# IrrigationManager.net
KiCad netlist of a schematic drawn in EAGLE
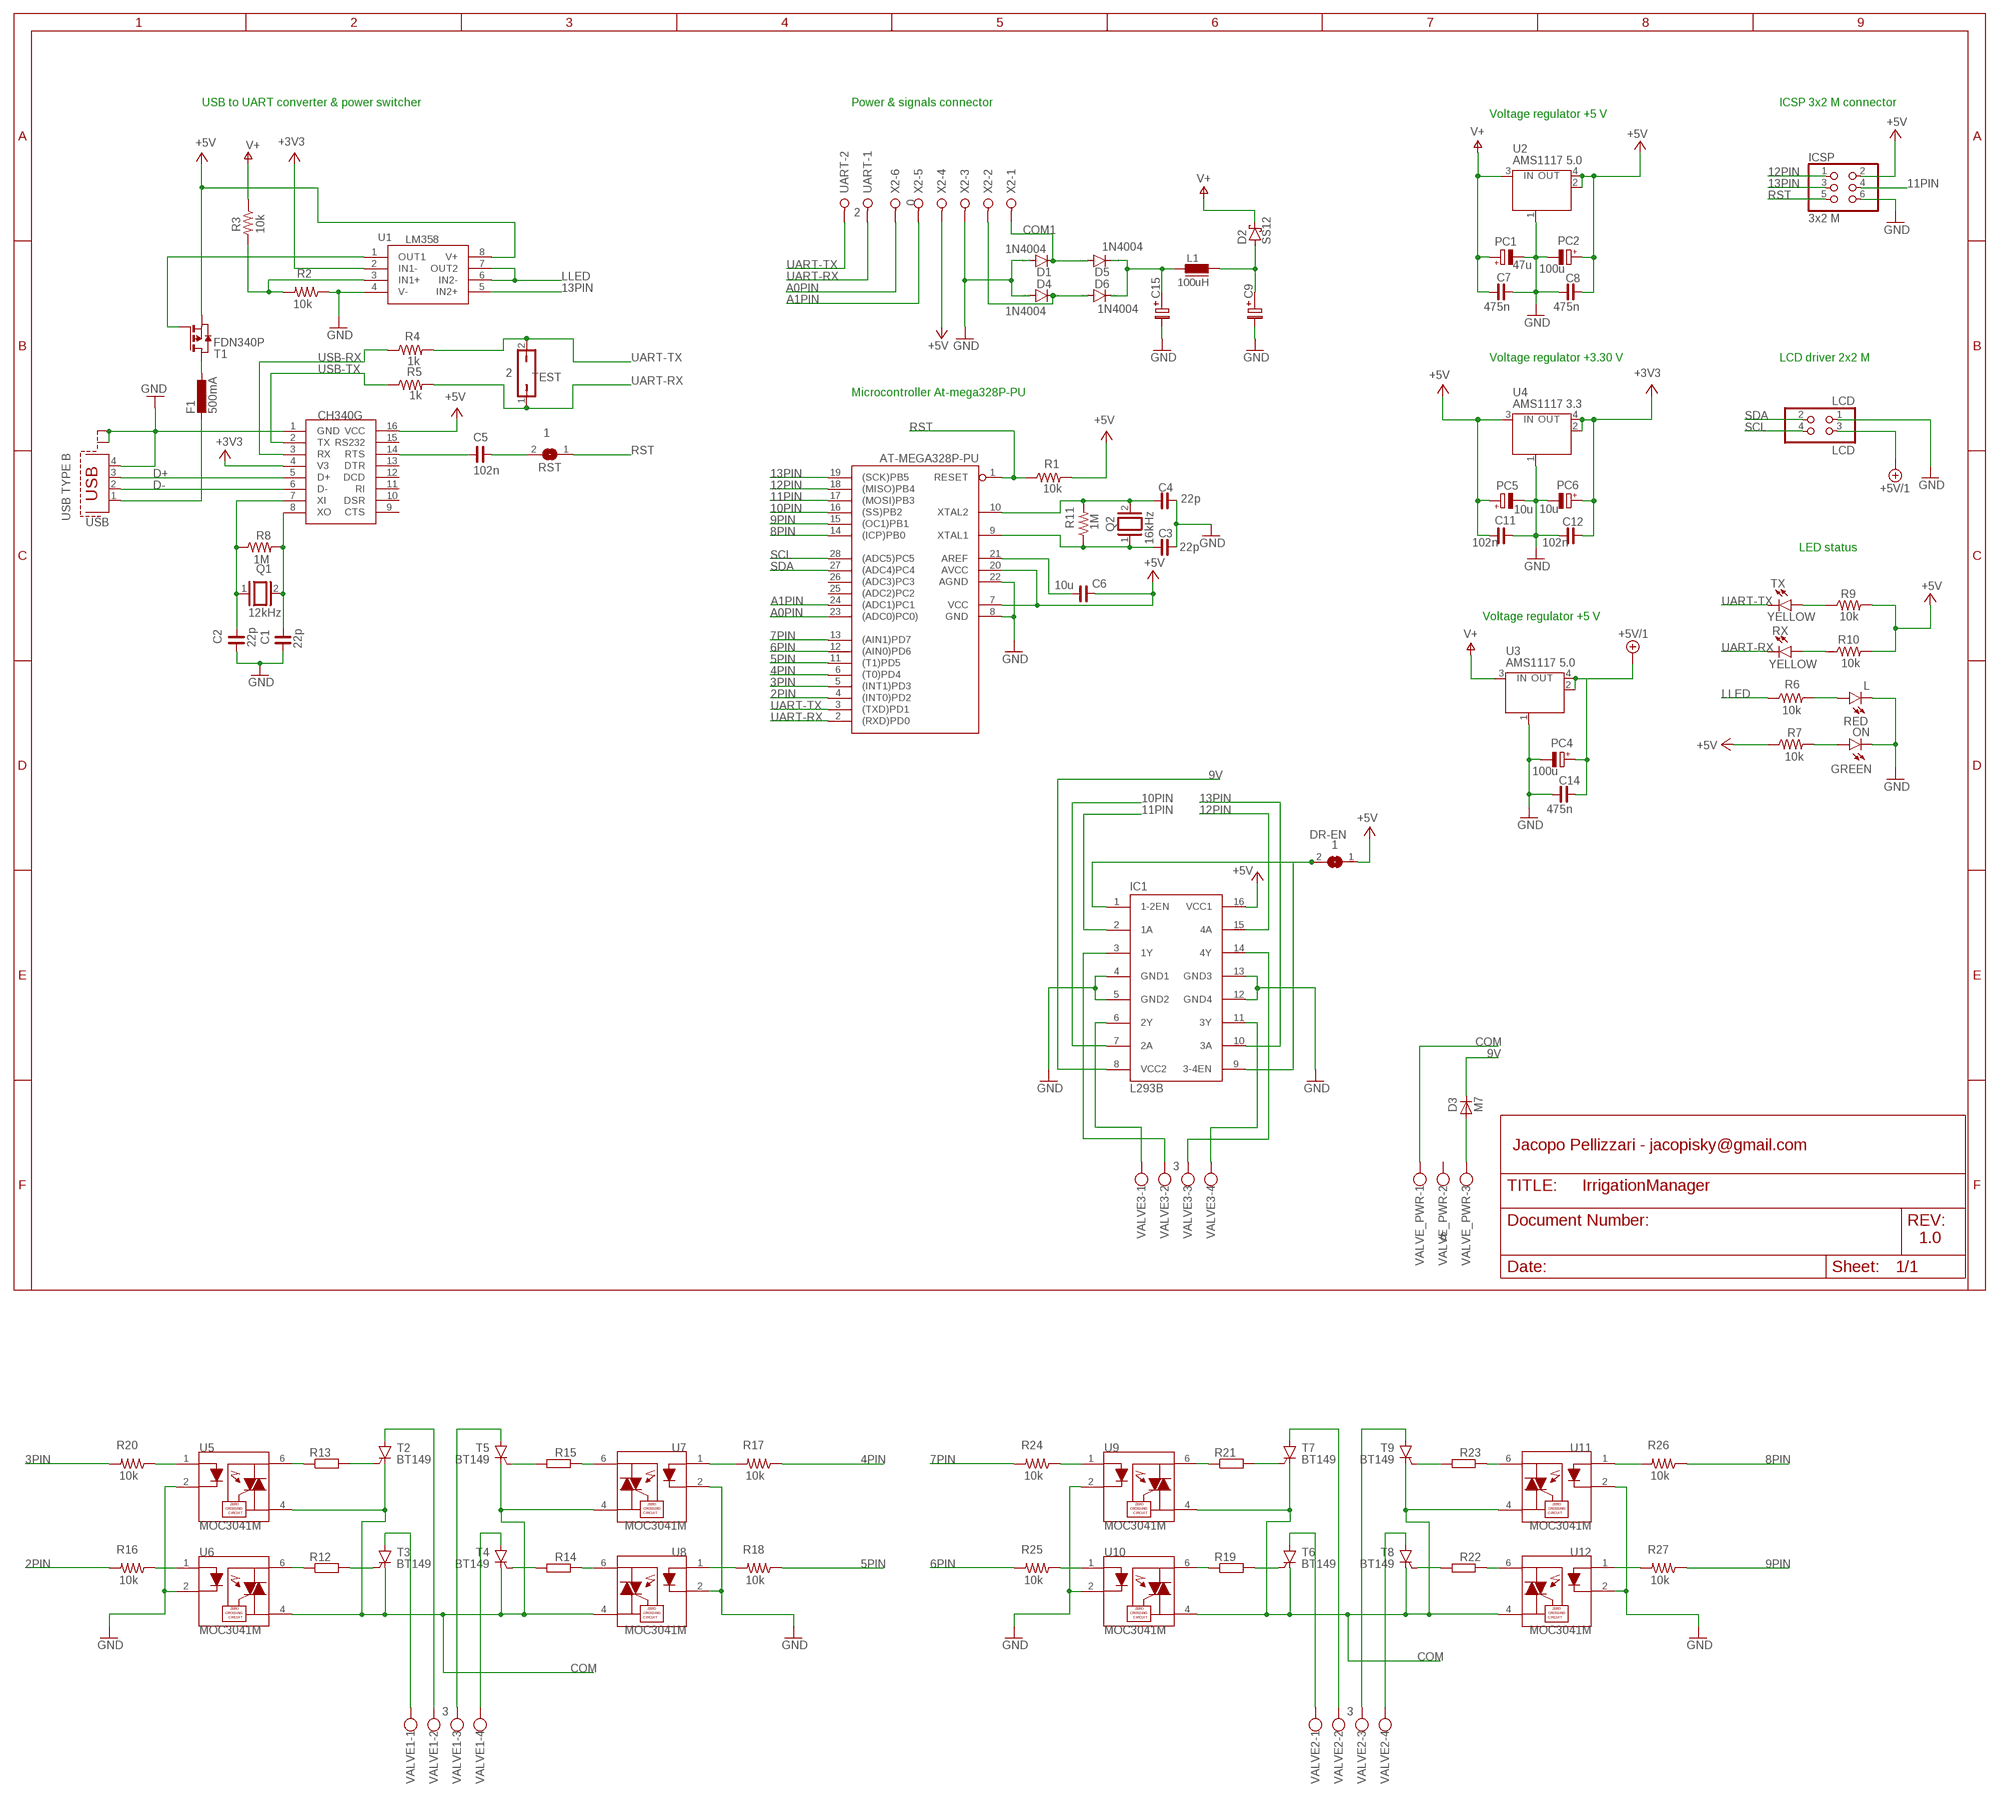
[diagram p0: schematic, sheet 1]

(export (version "E")
  (design (tool "Eeschema 10.0.6"))
  (components
    (comp (ref "AT-MEGA328P-PU")
      (value "ATMEGA328P-PU")
      (footprint "eagle-import:DIL28-3")
      (libsource (lib "eagle-import") (part "ATMEGA328P-PU"))
    )
    (comp (ref "C1")
      (value "22p")
      (footprint "eagle-import:C1206")
      (libsource (lib "eagle-import") (part "C_1206"))
    )
    (comp (ref "C2")
      (value "22p")
      (footprint "eagle-import:C1206")
      (libsource (lib "eagle-import") (part "C_1206"))
    )
    (comp (ref "C3")
      (value "22p")
      (footprint "eagle-import:C1206")
      (libsource (lib "eagle-import") (part "C_1206"))
    )
    (comp (ref "C4")
      (value "22p")
      (footprint "eagle-import:C1206")
      (libsource (lib "eagle-import") (part "C_1206"))
    )
    (comp (ref "C5")
      (value "102n")
      (footprint "eagle-import:C1206")
      (libsource (lib "eagle-import") (part "C_1206"))
    )
    (comp (ref "C6")
      (value "10u")
      (footprint "eagle-import:C1206")
      (libsource (lib "eagle-import") (part "C_1206"))
    )
    (comp (ref "C7")
      (value "475n")
      (footprint "eagle-import:C1206")
      (libsource (lib "eagle-import") (part "C_1206"))
    )
    (comp (ref "C8")
      (value "475n")
      (footprint "eagle-import:C1206")
      (libsource (lib "eagle-import") (part "C_1206"))
    )
    (comp (ref "C9")
      (value "C-PR-5,0X10")
      (footprint "eagle-import:E5,0-10")
      (libsource (lib "eagle-import") (part "C-PR-5,0X10"))
    )
    (comp (ref "C11")
      (value "102n")
      (footprint "eagle-import:C1206")
      (libsource (lib "eagle-import") (part "C_1206"))
    )
    (comp (ref "C12")
      (value "102n")
      (footprint "eagle-import:C1206")
      (libsource (lib "eagle-import") (part "C_1206"))
    )
    (comp (ref "C14")
      (value "475n")
      (footprint "eagle-import:C1206")
      (libsource (lib "eagle-import") (part "C_1206"))
    )
    (comp (ref "C15")
      (value "C-PR-5,0X10")
      (footprint "eagle-import:E5,0-10")
      (libsource (lib "eagle-import") (part "C-PR-5,0X10"))
    )
    (comp (ref "D1")
      (value "1N4004")
      (footprint "eagle-import:DO41-10")
      (libsource (lib "eagle-import") (part "1N4004"))
    )
    (comp (ref "D2")
      (value "SS12")
      (footprint "eagle-import:SMA")
      (fields
        (field (name "DIGIKEY_PART_NUMBER") "SS12FSCT-ND")
        (field (name "MANUFACTURER") "ON Semiconductor")
        (field (name "CREATED_BY") "PCBLayout.com")
      )
      (libsource (lib "eagle-import") (part "SS12"))
    )
    (comp (ref "D3")
      (value "M7")
      (footprint "eagle-import:SMB")
      (libsource (lib "eagle-import") (part "DIODE-SMB"))
    )
    (comp (ref "D4")
      (value "1N4004")
      (footprint "eagle-import:DO41-10")
      (libsource (lib "eagle-import") (part "1N4004"))
    )
    (comp (ref "D5")
      (value "1N4004")
      (footprint "eagle-import:DO41-10")
      (libsource (lib "eagle-import") (part "1N4004"))
    )
    (comp (ref "D6")
      (value "1N4004")
      (footprint "eagle-import:DO41-10")
      (libsource (lib "eagle-import") (part "1N4004"))
    )
    (comp (ref "DR-EN")
      (value "1")
      (footprint "eagle-import:SJ")
      (libsource (lib "eagle-import") (part "SJ"))
    )
    (comp (ref "F1")
      (value "500mA")
      (footprint "eagle-import:L1812")
      (libsource (lib "eagle-import") (part "L-EUL1812"))
    )
    (comp (ref "IC1")
      (value "L293B")
      (footprint "eagle-import:DIL16")
      (fields (field (name "MPN") "L293D"))
      (libsource (lib "eagle-import") (part "L293D"))
    )
    (comp (ref "ICSP")
      (value "3x2 M")
      (footprint "eagle-import:2X03")
      (libsource (lib "eagle-import") (part "PINHD-2X3"))
    )
    (comp (ref "L")
      (value "RED")
      (footprint "eagle-import:CHIPLED_1206")
      (libsource (lib "eagle-import") (part "LEDCHIPLED_1206"))
    )
    (comp (ref "L1")
      (value "100uH")
      (footprint "eagle-import:FASTRON_07HCP_INDUCTOR")
      (libsource (lib "eagle-import") (part "07HCP-4U7"))
    )
    (comp (ref "LCD")
      (value "LCD")
      (footprint "eagle-import:2X02")
      (libsource (lib "eagle-import") (part "PINHD-2X2"))
    )
    (comp (ref "ON")
      (value "GREEN")
      (footprint "eagle-import:CHIPLED_1206")
      (libsource (lib "eagle-import") (part "LEDCHIPLED_1206"))
    )
    (comp (ref "PC1")
      (value "47u")
      (footprint "eagle-import:PANASONIC_D")
      (libsource (lib "eagle-import") (part "CPOL-EUD"))
    )
    (comp (ref "PC2")
      (value "100u")
      (footprint "eagle-import:PANASONIC_D")
      (libsource (lib "eagle-import") (part "CPOL-EUD"))
    )
    (comp (ref "PC4")
      (value "100u")
      (footprint "eagle-import:PANASONIC_D")
      (libsource (lib "eagle-import") (part "CPOL-EUD"))
    )
    (comp (ref "PC5")
      (value "10u")
      (footprint "eagle-import:153CLV-0405")
      (libsource (lib "eagle-import") (part "rcl_334_CPOL-EU153CLV-0405"))
    )
    (comp (ref "PC6")
      (value "10u")
      (footprint "eagle-import:153CLV-0405")
      (libsource (lib "eagle-import") (part "rcl_334_CPOL-EU153CLV-0405"))
    )
    (comp (ref "Q1")
      (value "12kHz")
      (footprint "eagle-import:QS")
      (libsource (lib "eagle-import") (part "XTAL/S"))
    )
    (comp (ref "Q2")
      (value "16kHz")
      (footprint "eagle-import:QS")
      (libsource (lib "eagle-import") (part "XTAL/S"))
    )
    (comp (ref "R1")
      (value "10k")
      (footprint "eagle-import:RES_1206")
      (fields
        (field (name "DIGIKEY_PART_NUMBER") "P0.0ETR-ND")
        (field (name "MANUFACTURER") "Panasonic Electronic Components")
        (field (name "MPN") "ERJ-8GEY0R00V")
        (field (name "CREATED_BY") "PCBLayout.com")
      )
      (libsource (lib "eagle-import") (part "ERJ-8GEY0R00V"))
    )
    (comp (ref "R2")
      (value "10k")
      (footprint "eagle-import:RES_1206")
      (fields
        (field (name "DIGIKEY_PART_NUMBER") "P0.0ETR-ND")
        (field (name "MANUFACTURER") "Panasonic Electronic Components")
        (field (name "MPN") "ERJ-8GEY0R00V")
        (field (name "CREATED_BY") "PCBLayout.com")
      )
      (libsource (lib "eagle-import") (part "ERJ-8GEY0R00V"))
    )
    (comp (ref "R3")
      (value "10k")
      (footprint "eagle-import:RES_1206")
      (fields
        (field (name "DIGIKEY_PART_NUMBER") "P0.0ETR-ND")
        (field (name "MANUFACTURER") "Panasonic Electronic Components")
        (field (name "MPN") "ERJ-8GEY0R00V")
        (field (name "CREATED_BY") "PCBLayout.com")
      )
      (libsource (lib "eagle-import") (part "ERJ-8GEY0R00V"))
    )
    (comp (ref "R4")
      (value "1k")
      (footprint "eagle-import:RES_1206")
      (fields
        (field (name "DIGIKEY_PART_NUMBER") "P0.0ETR-ND")
        (field (name "MANUFACTURER") "Panasonic Electronic Components")
        (field (name "MPN") "ERJ-8GEY0R00V")
        (field (name "CREATED_BY") "PCBLayout.com")
      )
      (libsource (lib "eagle-import") (part "ERJ-8GEY0R00V"))
    )
    (comp (ref "R5")
      (value "1k")
      (footprint "eagle-import:RES_1206")
      (fields
        (field (name "DIGIKEY_PART_NUMBER") "P0.0ETR-ND")
        (field (name "MANUFACTURER") "Panasonic Electronic Components")
        (field (name "MPN") "ERJ-8GEY0R00V")
        (field (name "CREATED_BY") "PCBLayout.com")
      )
      (libsource (lib "eagle-import") (part "ERJ-8GEY0R00V"))
    )
    (comp (ref "R6")
      (value "10k")
      (footprint "eagle-import:RES_1206")
      (fields
        (field (name "DIGIKEY_PART_NUMBER") "P0.0ETR-ND")
        (field (name "MANUFACTURER") "Panasonic Electronic Components")
        (field (name "MPN") "ERJ-8GEY0R00V")
        (field (name "CREATED_BY") "PCBLayout.com")
      )
      (libsource (lib "eagle-import") (part "ERJ-8GEY0R00V"))
    )
    (comp (ref "R7")
      (value "10k")
      (footprint "eagle-import:RES_1206")
      (fields
        (field (name "DIGIKEY_PART_NUMBER") "P0.0ETR-ND")
        (field (name "MANUFACTURER") "Panasonic Electronic Components")
        (field (name "MPN") "ERJ-8GEY0R00V")
        (field (name "CREATED_BY") "PCBLayout.com")
      )
      (libsource (lib "eagle-import") (part "ERJ-8GEY0R00V"))
    )
    (comp (ref "R8")
      (value "1M")
      (footprint "eagle-import:RES_1206")
      (fields
        (field (name "DIGIKEY_PART_NUMBER") "P0.0ETR-ND")
        (field (name "MANUFACTURER") "Panasonic Electronic Components")
        (field (name "MPN") "ERJ-8GEY0R00V")
        (field (name "CREATED_BY") "PCBLayout.com")
      )
      (libsource (lib "eagle-import") (part "ERJ-8GEY0R00V"))
    )
    (comp (ref "R9")
      (value "10k")
      (footprint "eagle-import:RES_1206")
      (fields
        (field (name "DIGIKEY_PART_NUMBER") "P0.0ETR-ND")
        (field (name "MANUFACTURER") "Panasonic Electronic Components")
        (field (name "MPN") "ERJ-8GEY0R00V")
        (field (name "CREATED_BY") "PCBLayout.com")
      )
      (libsource (lib "eagle-import") (part "ERJ-8GEY0R00V"))
    )
    (comp (ref "R10")
      (value "10k")
      (footprint "eagle-import:RES_1206")
      (fields
        (field (name "DIGIKEY_PART_NUMBER") "P0.0ETR-ND")
        (field (name "MANUFACTURER") "Panasonic Electronic Components")
        (field (name "MPN") "ERJ-8GEY0R00V")
        (field (name "CREATED_BY") "PCBLayout.com")
      )
      (libsource (lib "eagle-import") (part "ERJ-8GEY0R00V"))
    )
    (comp (ref "R11")
      (value "1M")
      (footprint "eagle-import:RES_1206")
      (fields
        (field (name "DIGIKEY_PART_NUMBER") "P0.0ETR-ND")
        (field (name "MANUFACTURER") "Panasonic Electronic Components")
        (field (name "MPN") "ERJ-8GEY0R00V")
        (field (name "CREATED_BY") "PCBLayout.com")
      )
      (libsource (lib "eagle-import") (part "ERJ-8GEY0R00V"))
    )
    (comp (ref "R12")
      (value "R-EU_0204/7")
      (footprint "eagle-import:0204_7")
      (libsource (lib "eagle-import") (part "R-EU_0204/7"))
    )
    (comp (ref "R13")
      (value "R-EU_0204/7")
      (footprint "eagle-import:0204_7")
      (libsource (lib "eagle-import") (part "R-EU_0204/7"))
    )
    (comp (ref "R14")
      (value "R-EU_0204/7")
      (footprint "eagle-import:0204_7")
      (libsource (lib "eagle-import") (part "R-EU_0204/7"))
    )
    (comp (ref "R15")
      (value "R-EU_0204/7")
      (footprint "eagle-import:0204_7")
      (libsource (lib "eagle-import") (part "R-EU_0204/7"))
    )
    (comp (ref "R16")
      (value "10k")
      (footprint "eagle-import:RES_1206")
      (fields
        (field (name "DIGIKEY_PART_NUMBER") "P0.0ETR-ND")
        (field (name "MANUFACTURER") "Panasonic Electronic Components")
        (field (name "MPN") "ERJ-8GEY0R00V")
        (field (name "CREATED_BY") "PCBLayout.com")
      )
      (libsource (lib "eagle-import") (part "ERJ-8GEY0R00V"))
    )
    (comp (ref "R17")
      (value "10k")
      (footprint "eagle-import:RES_1206")
      (fields
        (field (name "DIGIKEY_PART_NUMBER") "P0.0ETR-ND")
        (field (name "MANUFACTURER") "Panasonic Electronic Components")
        (field (name "MPN") "ERJ-8GEY0R00V")
        (field (name "CREATED_BY") "PCBLayout.com")
      )
      (libsource (lib "eagle-import") (part "ERJ-8GEY0R00V"))
    )
    (comp (ref "R18")
      (value "10k")
      (footprint "eagle-import:RES_1206")
      (fields
        (field (name "DIGIKEY_PART_NUMBER") "P0.0ETR-ND")
        (field (name "MANUFACTURER") "Panasonic Electronic Components")
        (field (name "MPN") "ERJ-8GEY0R00V")
        (field (name "CREATED_BY") "PCBLayout.com")
      )
      (libsource (lib "eagle-import") (part "ERJ-8GEY0R00V"))
    )
    (comp (ref "R19")
      (value "R-EU_0204/7")
      (footprint "eagle-import:0204_7")
      (libsource (lib "eagle-import") (part "R-EU_0204/7"))
    )
    (comp (ref "R20")
      (value "10k")
      (footprint "eagle-import:RES_1206")
      (fields
        (field (name "DIGIKEY_PART_NUMBER") "P0.0ETR-ND")
        (field (name "MANUFACTURER") "Panasonic Electronic Components")
        (field (name "MPN") "ERJ-8GEY0R00V")
        (field (name "CREATED_BY") "PCBLayout.com")
      )
      (libsource (lib "eagle-import") (part "ERJ-8GEY0R00V"))
    )
    (comp (ref "R21")
      (value "R-EU_0204/7")
      (footprint "eagle-import:0204_7")
      (libsource (lib "eagle-import") (part "R-EU_0204/7"))
    )
    (comp (ref "R22")
      (value "R-EU_0204/7")
      (footprint "eagle-import:0204_7")
      (libsource (lib "eagle-import") (part "R-EU_0204/7"))
    )
    (comp (ref "R23")
      (value "R-EU_0204/7")
      (footprint "eagle-import:0204_7")
      (libsource (lib "eagle-import") (part "R-EU_0204/7"))
    )
    (comp (ref "R24")
      (value "10k")
      (footprint "eagle-import:RES_1206")
      (fields
        (field (name "DIGIKEY_PART_NUMBER") "P0.0ETR-ND")
        (field (name "MANUFACTURER") "Panasonic Electronic Components")
        (field (name "MPN") "ERJ-8GEY0R00V")
        (field (name "CREATED_BY") "PCBLayout.com")
      )
      (libsource (lib "eagle-import") (part "ERJ-8GEY0R00V"))
    )
    (comp (ref "R25")
      (value "10k")
      (footprint "eagle-import:RES_1206")
      (fields
        (field (name "DIGIKEY_PART_NUMBER") "P0.0ETR-ND")
        (field (name "MANUFACTURER") "Panasonic Electronic Components")
        (field (name "MPN") "ERJ-8GEY0R00V")
        (field (name "CREATED_BY") "PCBLayout.com")
      )
      (libsource (lib "eagle-import") (part "ERJ-8GEY0R00V"))
    )
    (comp (ref "R26")
      (value "10k")
      (footprint "eagle-import:RES_1206")
      (fields
        (field (name "DIGIKEY_PART_NUMBER") "P0.0ETR-ND")
        (field (name "MANUFACTURER") "Panasonic Electronic Components")
        (field (name "MPN") "ERJ-8GEY0R00V")
        (field (name "CREATED_BY") "PCBLayout.com")
      )
      (libsource (lib "eagle-import") (part "ERJ-8GEY0R00V"))
    )
    (comp (ref "R27")
      (value "10k")
      (footprint "eagle-import:RES_1206")
      (fields
        (field (name "DIGIKEY_PART_NUMBER") "P0.0ETR-ND")
        (field (name "MANUFACTURER") "Panasonic Electronic Components")
        (field (name "MPN") "ERJ-8GEY0R00V")
        (field (name "CREATED_BY") "PCBLayout.com")
      )
      (libsource (lib "eagle-import") (part "ERJ-8GEY0R00V"))
    )
    (comp (ref "RST") (value "1") (footprint "eagle-import:SJ") (libsource (lib "eagle-import") (part "SJ")))
    (comp (ref "RX")
      (value "YELLOW")
      (footprint "eagle-import:CHIPLED_1206")
      (libsource (lib "eagle-import") (part "LEDCHIPLED_1206"))
    )
    (comp (ref "T1")
      (value "FDN340P")
      (footprint "eagle-import:SOT-23")
      (libsource (lib "eagle-import") (part "PMOSSOT23"))
    )
    (comp (ref "T2")
      (value "BT149")
      (footprint "eagle-import:TO92-4")
      (libsource (lib "eagle-import") (part "BT149"))
    )
    (comp (ref "T3")
      (value "BT149")
      (footprint "eagle-import:TO92-4")
      (libsource (lib "eagle-import") (part "BT149"))
    )
    (comp (ref "T4")
      (value "BT149")
      (footprint "eagle-import:TO92-4")
      (libsource (lib "eagle-import") (part "BT149"))
    )
    (comp (ref "T5")
      (value "BT149")
      (footprint "eagle-import:TO92-4")
      (libsource (lib "eagle-import") (part "BT149"))
    )
    (comp (ref "T6")
      (value "BT149")
      (footprint "eagle-import:TO92-4")
      (libsource (lib "eagle-import") (part "BT149"))
    )
    (comp (ref "T7")
      (value "BT149")
      (footprint "eagle-import:TO92-4")
      (libsource (lib "eagle-import") (part "BT149"))
    )
    (comp (ref "T8")
      (value "BT149")
      (footprint "eagle-import:TO92-4")
      (libsource (lib "eagle-import") (part "BT149"))
    )
    (comp (ref "T9")
      (value "BT149")
      (footprint "eagle-import:TO92-4")
      (libsource (lib "eagle-import") (part "BT149"))
    )
    (comp (ref "TEST")
      (value "2")
      (footprint "eagle-import:JP1")
      (libsource (lib "eagle-import") (part "JP1Q"))
    )
    (comp (ref "TX")
      (value "YELLOW")
      (footprint "eagle-import:CHIPLED_1206")
      (libsource (lib "eagle-import") (part "LEDCHIPLED_1206"))
    )
    (comp (ref "U$1")
      (value "CH340G")
      (footprint "eagle-import:SOIC16")
      (libsource (lib "eagle-import") (part "CH340G"))
    )
    (comp (ref "U1")
      (value "LM358")
      (footprint "eagle-import:LM358DR")
      (fields
        (field (name "DIGIKEY_PART_NUMBER") "296-1014-1-ND")
        (field (name "MANUFACTURER") "Texas Instruments")
        (field (name "MPN") "LM358DR")
        (field (name "CREATED_BY") "PCBLayout.com")
      )
      (libsource (lib "eagle-import") (part "LM358DR"))
    )
    (comp (ref "U2")
      (value "AMS1117 5.0")
      (footprint "eagle-import:SOT223")
      (libsource (lib "eagle-import") (part "MC33269ST-3.3T3"))
    )
    (comp (ref "U3")
      (value "AMS1117 5.0")
      (footprint "eagle-import:SOT223")
      (libsource (lib "eagle-import") (part "MC33269ST-3.3T3"))
    )
    (comp (ref "U4")
      (value "AMS1117 3.3")
      (footprint "eagle-import:SOT223")
      (libsource (lib "eagle-import") (part "MC33269ST-3.3T3"))
    )
    (comp (ref "U5")
      (value "MOC3041M")
      (footprint "eagle-import:DIP762W46P254L889H508Q6")
      (fields (field (name "MF") "ON Semiconductor"))
      (libsource (lib "eagle-import") (part "MOC3041M"))
    )
    (comp (ref "U6")
      (value "MOC3041M")
      (footprint "eagle-import:DIP762W46P254L889H508Q6")
      (fields (field (name "MF") "ON Semiconductor"))
      (libsource (lib "eagle-import") (part "MOC3041M"))
    )
    (comp (ref "U7")
      (value "MOC3041M")
      (footprint "eagle-import:DIP762W46P254L889H508Q6")
      (fields (field (name "MF") "ON Semiconductor"))
      (libsource (lib "eagle-import") (part "MOC3041M"))
    )
    (comp (ref "U8")
      (value "MOC3041M")
      (footprint "eagle-import:DIP762W46P254L889H508Q6")
      (fields (field (name "MF") "ON Semiconductor"))
      (libsource (lib "eagle-import") (part "MOC3041M"))
    )
    (comp (ref "U9")
      (value "MOC3041M")
      (footprint "eagle-import:DIP762W46P254L889H508Q6")
      (fields (field (name "MF") "ON Semiconductor"))
      (libsource (lib "eagle-import") (part "MOC3041M"))
    )
    (comp (ref "U10")
      (value "MOC3041M")
      (footprint "eagle-import:DIP762W46P254L889H508Q6")
      (fields (field (name "MF") "ON Semiconductor"))
      (libsource (lib "eagle-import") (part "MOC3041M"))
    )
    (comp (ref "U11")
      (value "MOC3041M")
      (footprint "eagle-import:DIP762W46P254L889H508Q6")
      (fields (field (name "MF") "ON Semiconductor"))
      (libsource (lib "eagle-import") (part "MOC3041M"))
    )
    (comp (ref "U12")
      (value "MOC3041M")
      (footprint "eagle-import:DIP762W46P254L889H508Q6")
      (fields (field (name "MF") "ON Semiconductor"))
      (libsource (lib "eagle-import") (part "MOC3041M"))
    )
    (comp (ref "UART")
      (value "2")
      (footprint "eagle-import:W237-132")
      (libsource (lib "eagle-import") (part "W237-02P"))
    )
    (comp (ref "USB")
      (value "USB TYPE B")
      (footprint "eagle-import:PN61729-S")
      (libsource (lib "eagle-import") (part "PN61729-S"))
    )
    (comp (ref "VALVE1")
      (value "3")
      (footprint "eagle-import:W237-4P")
      (libsource (lib "eagle-import") (part "W237-04P"))
    )
    (comp (ref "VALVE2")
      (value "3")
      (footprint "eagle-import:W237-4P")
      (libsource (lib "eagle-import") (part "W237-04P"))
    )
    (comp (ref "VALVE3")
      (value "3")
      (footprint "eagle-import:W237-4P")
      (libsource (lib "eagle-import") (part "W237-04P"))
    )
    (comp (ref "VALVE_PWR")
      (value "6")
      (footprint "eagle-import:W237-133")
      (libsource (lib "eagle-import") (part "W237-03P"))
    )
    (comp (ref "X2")
      (value "0")
      (footprint "eagle-import:W237-6P")
      (libsource (lib "eagle-import") (part "W237-06P"))
    )
  )
  (nets
    (net (code "1") (name "+3V3") (class "Default")
      (node (ref "C12") (pin "2") (pinfunction "2_2") (pintype "passive"))
      (node (ref "PC6") (pin "+") (pinfunction "+_+") (pintype "passive"))
      (node (ref "U$1") (pin "4") (pinfunction "V3_4") (pintype "bidirectional"))
      (node (ref "U1") (pin "2") (pinfunction "IN1-_2") (pintype "input"))
      (node (ref "U4") (pin "2") (pinfunction "OUT_2") (pintype "passive"))
      (node (ref "U4") (pin "4") (pinfunction "OUT_4") (pintype "passive"))
    )
    (net (code "2") (name "+5V") (class "Default")
      (node (ref "AT-MEGA328P-PU") (pin "20") (pinfunction "AVCC_20") (pintype "power_in"))
      (node (ref "AT-MEGA328P-PU") (pin "7") (pinfunction "VCC_7") (pintype "power_in"))
      (node (ref "C11") (pin "1") (pinfunction "1_1") (pintype "passive"))
      (node (ref "C6") (pin "2") (pinfunction "2_2") (pintype "passive"))
      (node (ref "C8") (pin "2") (pinfunction "2_2") (pintype "passive"))
      (node (ref "DR-EN") (pin "1") (pinfunction "1_1") (pintype "passive"))
      (node (ref "IC1") (pin "16") (pinfunction "VCC1_16") (pintype "power_in"))
      (node (ref "ICSP") (pin "2") (pinfunction "2_2") (pintype "passive"))
      (node (ref "PC2") (pin "+") (pinfunction "+_+") (pintype "passive"))
      (node (ref "PC5") (pin "+") (pinfunction "+_+") (pintype "passive"))
      (node (ref "R1") (pin "2") (pinfunction "2_2") (pintype "passive"))
      (node (ref "R10") (pin "2") (pinfunction "2_2") (pintype "passive"))
      (node (ref "R7") (pin "1") (pinfunction "1_1") (pintype "passive"))
      (node (ref "R9") (pin "2") (pinfunction "2_2") (pintype "passive"))
      (node (ref "T1") (pin "2") (pinfunction "S_2") (pintype "passive"))
      (node (ref "U$1") (pin "16") (pinfunction "VCC_16") (pintype "bidirectional"))
      (node (ref "U1") (pin "8") (pinfunction "V+_8") (pintype "power_in"))
      (node (ref "U2") (pin "2") (pinfunction "OUT_2") (pintype "passive"))
      (node (ref "U2") (pin "4") (pinfunction "OUT_4") (pintype "passive"))
      (node (ref "U4") (pin "3") (pinfunction "IN_3") (pintype "input"))
      (node (ref "X2") (pin "4") (pinfunction "KL_4") (pintype "passive"))
    )
    (net (code "3") (name "+5V{slash}1") (class "Default")
      (node (ref "C14") (pin "2") (pinfunction "2_2") (pintype "passive"))
      (node (ref "LCD") (pin "3") (pinfunction "3_3") (pintype "passive"))
      (node (ref "PC4") (pin "+") (pinfunction "+_+") (pintype "passive"))
      (node (ref "U3") (pin "2") (pinfunction "OUT_2") (pintype "passive"))
      (node (ref "U3") (pin "4") (pinfunction "OUT_4") (pintype "passive"))
    )
    (net (code "4") (name "/2PIN") (class "Default")
      (node (ref "AT-MEGA328P-PU") (pin "4") (pinfunction "(INT0)PD2_4") (pintype "bidirectional"))
      (node (ref "R16") (pin "2") (pinfunction "2_2") (pintype "passive"))
    )
    (net (code "5") (name "/3PIN") (class "Default")
      (node (ref "AT-MEGA328P-PU") (pin "5") (pinfunction "(INT1)PD3_5") (pintype "bidirectional"))
      (node (ref "R20") (pin "2") (pinfunction "2_2") (pintype "passive"))
    )
    (net (code "6") (name "/4PIN") (class "Default")
      (node (ref "AT-MEGA328P-PU") (pin "6") (pinfunction "(T0)PD4_6") (pintype "bidirectional"))
      (node (ref "R17") (pin "1") (pinfunction "1_1") (pintype "passive"))
    )
    (net (code "7") (name "/5PIN") (class "Default")
      (node (ref "AT-MEGA328P-PU") (pin "11") (pinfunction "(T1)PD5_11") (pintype "bidirectional"))
      (node (ref "R18") (pin "1") (pinfunction "1_1") (pintype "passive"))
    )
    (net (code "8") (name "/6PIN") (class "Default")
      (node (ref "AT-MEGA328P-PU") (pin "12") (pinfunction "(AIN0)PD6_12") (pintype "bidirectional"))
      (node (ref "R25") (pin "2") (pinfunction "2_2") (pintype "passive"))
    )
    (net (code "9") (name "/7PIN") (class "Default")
      (node (ref "AT-MEGA328P-PU") (pin "13") (pinfunction "(AIN1)PD7_13") (pintype "bidirectional"))
      (node (ref "R24") (pin "2") (pinfunction "2_2") (pintype "passive"))
    )
    (net (code "10") (name "/8PIN") (class "Default")
      (node (ref "AT-MEGA328P-PU") (pin "14") (pinfunction "(ICP)PB0_14") (pintype "bidirectional"))
      (node (ref "R26") (pin "1") (pinfunction "1_1") (pintype "passive"))
    )
    (net (code "11") (name "/9PIN") (class "Default")
      (node (ref "AT-MEGA328P-PU") (pin "15") (pinfunction "(OC1)PB1_15") (pintype "bidirectional"))
      (node (ref "R27") (pin "1") (pinfunction "1_1") (pintype "passive"))
    )
    (net (code "12") (name "/9V") (class "Default")
      (node (ref "D3") (pin "C") (pinfunction "C_C") (pintype "passive"))
      (node (ref "IC1") (pin "8") (pinfunction "VCC2_8") (pintype "power_in"))
    )
    (net (code "13") (name "/10PIN") (class "Default")
      (node (ref "AT-MEGA328P-PU") (pin "16") (pinfunction "(SS)PB2_16") (pintype "bidirectional"))
      (node (ref "IC1") (pin "7") (pinfunction "2A_7") (pintype "input"))
    )
    (net (code "14") (name "/11PIN") (class "Default")
      (node (ref "AT-MEGA328P-PU") (pin "17") (pinfunction "(MOSI)PB3_17") (pintype "bidirectional"))
      (node (ref "IC1") (pin "2") (pinfunction "1A_2") (pintype "input"))
      (node (ref "ICSP") (pin "4") (pinfunction "4_4") (pintype "passive"))
    )
    (net (code "15") (name "/12PIN") (class "Default")
      (node (ref "AT-MEGA328P-PU") (pin "18") (pinfunction "(MISO)PB4_18") (pintype "bidirectional"))
      (node (ref "IC1") (pin "15") (pinfunction "4A_15") (pintype "input"))
      (node (ref "ICSP") (pin "1") (pinfunction "1_1") (pintype "passive"))
    )
    (net (code "16") (name "/13PIN") (class "Default")
      (node (ref "AT-MEGA328P-PU") (pin "19") (pinfunction "(SCK)PB5_19") (pintype "bidirectional"))
      (node (ref "IC1") (pin "10") (pinfunction "3A_10") (pintype "input"))
      (node (ref "ICSP") (pin "3") (pinfunction "3_3") (pintype "passive"))
      (node (ref "U1") (pin "5") (pinfunction "IN2+_5") (pintype "input"))
    )
    (net (code "17") (name "/A0PIN") (class "Default")
      (node (ref "AT-MEGA328P-PU") (pin "23") (pinfunction "(ADC0)PC0)_23") (pintype "bidirectional"))
      (node (ref "X2") (pin "6") (pinfunction "KL_6") (pintype "passive"))
    )
    (net (code "18") (name "/A1PIN") (class "Default")
      (node (ref "AT-MEGA328P-PU") (pin "24") (pinfunction "(ADC1)PC1_24") (pintype "bidirectional"))
      (node (ref "X2") (pin "5") (pinfunction "KL_5") (pintype "passive"))
    )
    (net (code "19") (name "/COM") (class "Default")
      (node (ref "T2") (pin "C") (pinfunction "C_C") (pintype "passive"))
      (node (ref "T3") (pin "C") (pinfunction "C_C") (pintype "passive"))
      (node (ref "T4") (pin "C") (pinfunction "C_C") (pintype "passive"))
      (node (ref "T5") (pin "C") (pinfunction "C_C") (pintype "passive"))
      (node (ref "T6") (pin "C") (pinfunction "C_C") (pintype "passive"))
      (node (ref "T7") (pin "C") (pinfunction "C_C") (pintype "passive"))
      (node (ref "T8") (pin "C") (pinfunction "C_C") (pintype "passive"))
      (node (ref "T9") (pin "C") (pinfunction "C_C") (pintype "passive"))
      (node (ref "U10") (pin "4") (pinfunction "MT1_4") (pintype "passive"))
      (node (ref "U11") (pin "4") (pinfunction "MT1_4") (pintype "passive"))
      (node (ref "U12") (pin "4") (pinfunction "MT1_4") (pintype "passive"))
      (node (ref "U5") (pin "4") (pinfunction "MT1_4") (pintype "passive"))
      (node (ref "U6") (pin "4") (pinfunction "MT1_4") (pintype "passive"))
      (node (ref "U7") (pin "4") (pinfunction "MT1_4") (pintype "passive"))
      (node (ref "U8") (pin "4") (pinfunction "MT1_4") (pintype "passive"))
      (node (ref "U9") (pin "4") (pinfunction "MT1_4") (pintype "passive"))
      (node (ref "VALVE_PWR") (pin "1") (pinfunction "KL_1") (pintype "passive"))
    )
    (net (code "20") (name "/COM1") (class "Default")
      (node (ref "D1") (pin "C") (pinfunction "C_C") (pintype "passive"))
      (node (ref "D5") (pin "A") (pinfunction "A_A") (pintype "passive"))
      (node (ref "X2") (pin "1") (pinfunction "KL_1") (pintype "passive"))
    )
    (net (code "21") (name "/D+") (class "Default")
      (node (ref "U$1") (pin "5") (pinfunction "D+_5") (pintype "bidirectional"))
      (node (ref "USB") (pin "3") (pinfunction "3_3") (pintype "passive"))
    )
    (net (code "22") (name "/D-") (class "Default")
      (node (ref "U$1") (pin "6") (pinfunction "D-_6") (pintype "bidirectional"))
      (node (ref "USB") (pin "2") (pinfunction "2_2") (pintype "passive"))
    )
    (net (code "23") (name "/LLED") (class "Default")
      (node (ref "R6") (pin "1") (pinfunction "1_1") (pintype "passive"))
      (node (ref "U1") (pin "6") (pinfunction "IN2-_6") (pintype "input"))
      (node (ref "U1") (pin "7") (pinfunction "OUT2_7") (pintype "output"))
    )
    (net (code "24") (name "/RST") (class "Default")
      (node (ref "AT-MEGA328P-PU") (pin "1") (pinfunction "RESET_1") (pintype "input"))
      (node (ref "ICSP") (pin "5") (pinfunction "5_5") (pintype "passive"))
      (node (ref "R1") (pin "1") (pinfunction "1_1") (pintype "passive"))
      (node (ref "RST") (pin "1") (pinfunction "1_1") (pintype "passive"))
    )
    (net (code "25") (name "/SCL") (class "Default")
      (node (ref "AT-MEGA328P-PU") (pin "28") (pinfunction "(ADC5)PC5_28") (pintype "bidirectional"))
      (node (ref "LCD") (pin "4") (pinfunction "4_4") (pintype "passive"))
    )
    (net (code "26") (name "/SDA") (class "Default")
      (node (ref "AT-MEGA328P-PU") (pin "27") (pinfunction "(ADC4)PC4_27") (pintype "bidirectional"))
      (node (ref "LCD") (pin "2") (pinfunction "2_2") (pintype "passive"))
    )
    (net (code "27") (name "/UART-RX") (class "Default")
      (node (ref "AT-MEGA328P-PU") (pin "2") (pinfunction "(RXD)PD0_2") (pintype "bidirectional"))
      (node (ref "R5") (pin "2") (pinfunction "2_2") (pintype "passive"))
      (node (ref "RX") (pin "C") (pinfunction "C_C") (pintype "passive"))
      (node (ref "TEST") (pin "1") (pinfunction "1_1") (pintype "passive"))
      (node (ref "UART") (pin "1") (pinfunction "KL_1") (pintype "passive"))
    )
    (net (code "28") (name "/UART-TX") (class "Default")
      (node (ref "AT-MEGA328P-PU") (pin "3") (pinfunction "(TXD)PD1_3") (pintype "bidirectional"))
      (node (ref "R4") (pin "2") (pinfunction "2_2") (pintype "passive"))
      (node (ref "TEST") (pin "2") (pinfunction "2_2") (pintype "passive"))
      (node (ref "TX") (pin "C") (pinfunction "C_C") (pintype "passive"))
      (node (ref "UART") (pin "2") (pinfunction "KL_2") (pintype "passive"))
    )
    (net (code "29") (name "/USB-RX") (class "Default")
      (node (ref "R4") (pin "1") (pinfunction "1_1") (pintype "passive"))
      (node (ref "U$1") (pin "3") (pinfunction "RX_3") (pintype "bidirectional"))
    )
    (net (code "30") (name "/USB-TX") (class "Default")
      (node (ref "R5") (pin "1") (pinfunction "1_1") (pintype "passive"))
      (node (ref "U$1") (pin "2") (pinfunction "TX_2") (pintype "bidirectional"))
    )
    (net (code "31") (name "GND") (class "Default")
      (node (ref "AT-MEGA328P-PU") (pin "22") (pinfunction "AGND_22") (pintype "power_in"))
      (node (ref "AT-MEGA328P-PU") (pin "8") (pinfunction "GND_8") (pintype "power_in"))
      (node (ref "C1") (pin "1") (pinfunction "1_1") (pintype "passive"))
      (node (ref "C11") (pin "2") (pinfunction "2_2") (pintype "passive"))
      (node (ref "C12") (pin "1") (pinfunction "1_1") (pintype "passive"))
      (node (ref "C14") (pin "1") (pinfunction "1_1") (pintype "passive"))
      (node (ref "C15") (pin "-") (pinfunction "-_-") (pintype "passive"))
      (node (ref "C2") (pin "1") (pinfunction "1_1") (pintype "passive"))
      (node (ref "C3") (pin "2") (pinfunction "2_2") (pintype "passive"))
      (node (ref "C4") (pin "2") (pinfunction "2_2") (pintype "passive"))
      (node (ref "C7") (pin "2") (pinfunction "2_2") (pintype "passive"))
      (node (ref "C8") (pin "1") (pinfunction "1_1") (pintype "passive"))
      (node (ref "C9") (pin "-") (pinfunction "-_-") (pintype "passive"))
      (node (ref "D1") (pin "A") (pinfunction "A_A") (pintype "passive"))
      (node (ref "D4") (pin "A") (pinfunction "A_A") (pintype "passive"))
      (node (ref "IC1") (pin "12") (pinfunction "GND4_12") (pintype "power_in"))
      (node (ref "IC1") (pin "13") (pinfunction "GND3_13") (pintype "power_in"))
      (node (ref "IC1") (pin "4") (pinfunction "GND1_4") (pintype "power_in"))
      (node (ref "IC1") (pin "5") (pinfunction "GND2_5") (pintype "power_in"))
      (node (ref "ICSP") (pin "6") (pinfunction "6_6") (pintype "passive"))
      (node (ref "L") (pin "C") (pinfunction "C_C") (pintype "passive"))
      (node (ref "LCD") (pin "1") (pinfunction "1_1") (pintype "passive"))
      (node (ref "ON") (pin "C") (pinfunction "C_C") (pintype "passive"))
      (node (ref "PC1") (pin "-") (pinfunction "-_-") (pintype "passive"))
      (node (ref "PC2") (pin "-") (pinfunction "-_-") (pintype "passive"))
      (node (ref "PC4") (pin "-") (pinfunction "-_-") (pintype "passive"))
      (node (ref "PC5") (pin "-") (pinfunction "-_-") (pintype "passive"))
      (node (ref "PC6") (pin "-") (pinfunction "-_-") (pintype "passive"))
      (node (ref "R2") (pin "1") (pinfunction "1_1") (pintype "passive"))
      (node (ref "U$1") (pin "1") (pinfunction "GND_1") (pintype "bidirectional"))
      (node (ref "U1") (pin "4") (pinfunction "V-_4") (pintype "power_in"))
      (node (ref "U10") (pin "2") (pinfunction "C_2") (pintype "passive"))
      (node (ref "U11") (pin "2") (pinfunction "C_2") (pintype "passive"))
      (node (ref "U12") (pin "2") (pinfunction "C_2") (pintype "passive"))
      (node (ref "U2") (pin "1") (pinfunction "GND/ADJ_1") (pintype "input"))
      (node (ref "U3") (pin "1") (pinfunction "GND/ADJ_1") (pintype "input"))
      (node (ref "U4") (pin "1") (pinfunction "GND/ADJ_1") (pintype "input"))
      (node (ref "U5") (pin "2") (pinfunction "C_2") (pintype "passive"))
      (node (ref "U6") (pin "2") (pinfunction "C_2") (pintype "passive"))
      (node (ref "U7") (pin "2") (pinfunction "C_2") (pintype "passive"))
      (node (ref "U8") (pin "2") (pinfunction "C_2") (pintype "passive"))
      (node (ref "U9") (pin "2") (pinfunction "C_2") (pintype "passive"))
      (node (ref "USB") (pin "4") (pinfunction "4_4") (pintype "passive"))
      (node (ref "USB") (pin "S1") (pinfunction "S1_S1") (pintype "passive"))
      (node (ref "USB") (pin "S2") (pinfunction "S2_S2") (pintype "passive"))
      (node (ref "X2") (pin "3") (pinfunction "KL_3") (pintype "passive"))
    )
    (net (code "32") (name "Net-(AT-MEGA328P-PU-AREF)") (class "Default")
      (node (ref "AT-MEGA328P-PU") (pin "21") (pinfunction "AREF_21") (pintype "passive"))
      (node (ref "C6") (pin "1") (pinfunction "1_1") (pintype "passive"))
    )
    (net (code "33") (name "Net-(AT-MEGA328P-PU-XTAL1)") (class "Default")
      (node (ref "AT-MEGA328P-PU") (pin "9") (pinfunction "XTAL1_9") (pintype "bidirectional"))
      (node (ref "C3") (pin "1") (pinfunction "1_1") (pintype "passive"))
      (node (ref "Q2") (pin "1") (pinfunction "1_1") (pintype "passive"))
      (node (ref "R11") (pin "1") (pinfunction "1_1") (pintype "passive"))
    )
    (net (code "34") (name "Net-(AT-MEGA328P-PU-XTAL2)") (class "Default")
      (node (ref "AT-MEGA328P-PU") (pin "10") (pinfunction "XTAL2_10") (pintype "bidirectional"))
      (node (ref "C4") (pin "1") (pinfunction "1_1") (pintype "passive"))
      (node (ref "Q2") (pin "2") (pinfunction "2_2") (pintype "passive"))
      (node (ref "R11") (pin "2") (pinfunction "2_2") (pintype "passive"))
    )
    (net (code "35") (name "Net-(C5-Pad2)") (class "Default")
      (node (ref "C5") (pin "2") (pinfunction "2_2") (pintype "passive"))
      (node (ref "RST") (pin "2") (pinfunction "2_2") (pintype "passive"))
    )
    (net (code "36") (name "Net-(C9-Pad+)") (class "Default")
      (node (ref "C9") (pin "+") (pinfunction "+_+") (pintype "passive"))
      (node (ref "D2") (pin "A") (pinfunction "A_A") (pintype "passive"))
      (node (ref "L1") (pin "2") (pinfunction "2_2") (pintype "passive"))
    )
    (net (code "37") (name "Net-(C15-Pad+)") (class "Default")
      (node (ref "C15") (pin "+") (pinfunction "+_+") (pintype "passive"))
      (node (ref "D5") (pin "C") (pinfunction "C_C") (pintype "passive"))
      (node (ref "D6") (pin "C") (pinfunction "C_C") (pintype "passive"))
      (node (ref "L1") (pin "1") (pinfunction "1_1") (pintype "passive"))
    )
    (net (code "38") (name "Net-(F1-Pad2)") (class "Default")
      (node (ref "F1") (pin "2") (pinfunction "2_2") (pintype "passive"))
      (node (ref "USB") (pin "1") (pinfunction "1_1") (pintype "passive"))
    )
    (net (code "39") (name "Net-(IC1-1-2EN)") (class "Default")
      (node (ref "DR-EN") (pin "2") (pinfunction "2_2") (pintype "passive"))
      (node (ref "IC1") (pin "1") (pinfunction "1-2EN_1") (pintype "input"))
      (node (ref "IC1") (pin "9") (pinfunction "3-4EN_9") (pintype "input"))
    )
    (net (code "40") (name "Net-(IC1-1Y)") (class "Default")
      (node (ref "IC1") (pin "3") (pinfunction "1Y_3") (pintype "output"))
      (node (ref "VALVE3") (pin "2") (pinfunction "KL_2") (pintype "passive"))
    )
    (net (code "41") (name "Net-(IC1-2Y)") (class "Default")
      (node (ref "IC1") (pin "6") (pinfunction "2Y_6") (pintype "output"))
      (node (ref "VALVE3") (pin "1") (pinfunction "KL_1") (pintype "passive"))
    )
    (net (code "42") (name "Net-(IC1-3Y)") (class "Default")
      (node (ref "IC1") (pin "11") (pinfunction "3Y_11") (pintype "output"))
      (node (ref "VALVE3") (pin "4") (pinfunction "KL_4") (pintype "passive"))
    )
    (net (code "43") (name "Net-(IC1-4Y)") (class "Default")
      (node (ref "IC1") (pin "14") (pinfunction "4Y_14") (pintype "output"))
      (node (ref "VALVE3") (pin "3") (pinfunction "KL_3") (pintype "passive"))
    )
    (net (code "44") (name "Net-(L-PadA)") (class "Default")
      (node (ref "L") (pin "A") (pinfunction "A_A") (pintype "passive"))
      (node (ref "R6") (pin "2") (pinfunction "2_2") (pintype "passive"))
    )
    (net (code "45") (name "Net-(ON-PadA)") (class "Default")
      (node (ref "ON") (pin "A") (pinfunction "A_A") (pintype "passive"))
      (node (ref "R7") (pin "2") (pinfunction "2_2") (pintype "passive"))
    )
    (net (code "46") (name "Net-(R9-Pad1)") (class "Default")
      (node (ref "R9") (pin "1") (pinfunction "1_1") (pintype "passive"))
      (node (ref "TX") (pin "A") (pinfunction "A_A") (pintype "passive"))
    )
    (net (code "47") (name "Net-(R10-Pad1)") (class "Default")
      (node (ref "R10") (pin "1") (pinfunction "1_1") (pintype "passive"))
      (node (ref "RX") (pin "A") (pinfunction "A_A") (pintype "passive"))
    )
    (net (code "48") (name "Net-(R12-Pad2)") (class "Default")
      (node (ref "R12") (pin "2") (pinfunction "2_2") (pintype "passive"))
      (node (ref "T3") (pin "G") (pinfunction "G_G") (pintype "passive"))
    )
    (net (code "49") (name "Net-(R13-Pad2)") (class "Default")
      (node (ref "R13") (pin "2") (pinfunction "2_2") (pintype "passive"))
      (node (ref "T2") (pin "G") (pinfunction "G_G") (pintype "passive"))
    )
    (net (code "50") (name "Net-(R14-Pad2)") (class "Default")
      (node (ref "R14") (pin "2") (pinfunction "2_2") (pintype "passive"))
      (node (ref "T4") (pin "G") (pinfunction "G_G") (pintype "passive"))
    )
    (net (code "51") (name "Net-(R15-Pad2)") (class "Default")
      (node (ref "R15") (pin "2") (pinfunction "2_2") (pintype "passive"))
      (node (ref "T5") (pin "G") (pinfunction "G_G") (pintype "passive"))
    )
    (net (code "52") (name "Net-(R19-Pad2)") (class "Default")
      (node (ref "R19") (pin "2") (pinfunction "2_2") (pintype "passive"))
      (node (ref "T6") (pin "G") (pinfunction "G_G") (pintype "passive"))
    )
    (net (code "53") (name "Net-(R21-Pad2)") (class "Default")
      (node (ref "R21") (pin "2") (pinfunction "2_2") (pintype "passive"))
      (node (ref "T7") (pin "G") (pinfunction "G_G") (pintype "passive"))
    )
    (net (code "54") (name "Net-(R22-Pad2)") (class "Default")
      (node (ref "R22") (pin "2") (pinfunction "2_2") (pintype "passive"))
      (node (ref "T8") (pin "G") (pinfunction "G_G") (pintype "passive"))
    )
    (net (code "55") (name "Net-(R23-Pad2)") (class "Default")
      (node (ref "R23") (pin "2") (pinfunction "2_2") (pintype "passive"))
      (node (ref "T9") (pin "G") (pinfunction "G_G") (pintype "passive"))
    )
    (net (code "56") (name "Net-(T1-D)") (class "Default")
      (node (ref "F1") (pin "1") (pinfunction "1_1") (pintype "passive"))
      (node (ref "T1") (pin "1") (pinfunction "D_1") (pintype "passive"))
    )
    (net (code "57") (name "Net-(T1-G)") (class "Default")
      (node (ref "T1") (pin "3") (pinfunction "G_3") (pintype "passive"))
      (node (ref "U1") (pin "1") (pinfunction "OUT1_1") (pintype "output"))
    )
    (net (code "58") (name "Net-(U$1-RTS)") (class "Default")
      (node (ref "C5") (pin "1") (pinfunction "1_1") (pintype "passive"))
      (node (ref "U$1") (pin "14") (pinfunction "RTS_14") (pintype "bidirectional"))
    )
    (net (code "59") (name "Net-(U$1-XI)") (class "Default")
      (node (ref "C2") (pin "2") (pinfunction "2_2") (pintype "passive"))
      (node (ref "Q1") (pin "1") (pinfunction "1_1") (pintype "passive"))
      (node (ref "R8") (pin "1") (pinfunction "1_1") (pintype "passive"))
      (node (ref "U$1") (pin "7") (pinfunction "XI_7") (pintype "bidirectional"))
    )
    (net (code "60") (name "Net-(U$1-XO)") (class "Default")
      (node (ref "C1") (pin "2") (pinfunction "2_2") (pintype "passive"))
      (node (ref "Q1") (pin "2") (pinfunction "2_2") (pintype "passive"))
      (node (ref "R8") (pin "2") (pinfunction "2_2") (pintype "passive"))
      (node (ref "U$1") (pin "8") (pinfunction "XO_8") (pintype "bidirectional"))
    )
    (net (code "61") (name "Net-(U1-IN1+)") (class "Default")
      (node (ref "R2") (pin "2") (pinfunction "2_2") (pintype "passive"))
      (node (ref "R3") (pin "2") (pinfunction "2_2") (pintype "passive"))
      (node (ref "U1") (pin "3") (pinfunction "IN1+_3") (pintype "input"))
    )
    (net (code "62") (name "Net-(U5-A)") (class "Default")
      (node (ref "R20") (pin "1") (pinfunction "1_1") (pintype "passive"))
      (node (ref "U5") (pin "1") (pinfunction "A_1") (pintype "passive"))
    )
    (net (code "63") (name "Net-(U5-MT2)") (class "Default")
      (node (ref "R13") (pin "1") (pinfunction "1_1") (pintype "passive"))
      (node (ref "U5") (pin "6") (pinfunction "MT2_6") (pintype "passive"))
    )
    (net (code "64") (name "Net-(U6-A)") (class "Default")
      (node (ref "R16") (pin "1") (pinfunction "1_1") (pintype "passive"))
      (node (ref "U6") (pin "1") (pinfunction "A_1") (pintype "passive"))
    )
    (net (code "65") (name "Net-(U6-MT2)") (class "Default")
      (node (ref "R12") (pin "1") (pinfunction "1_1") (pintype "passive"))
      (node (ref "U6") (pin "6") (pinfunction "MT2_6") (pintype "passive"))
    )
    (net (code "66") (name "Net-(U7-A)") (class "Default")
      (node (ref "R17") (pin "2") (pinfunction "2_2") (pintype "passive"))
      (node (ref "U7") (pin "1") (pinfunction "A_1") (pintype "passive"))
    )
    (net (code "67") (name "Net-(U7-MT2)") (class "Default")
      (node (ref "R15") (pin "1") (pinfunction "1_1") (pintype "passive"))
      (node (ref "U7") (pin "6") (pinfunction "MT2_6") (pintype "passive"))
    )
    (net (code "68") (name "Net-(U8-A)") (class "Default")
      (node (ref "R18") (pin "2") (pinfunction "2_2") (pintype "passive"))
      (node (ref "U8") (pin "1") (pinfunction "A_1") (pintype "passive"))
    )
    (net (code "69") (name "Net-(U8-MT2)") (class "Default")
      (node (ref "R14") (pin "1") (pinfunction "1_1") (pintype "passive"))
      (node (ref "U8") (pin "6") (pinfunction "MT2_6") (pintype "passive"))
    )
    (net (code "70") (name "Net-(U9-A)") (class "Default")
      (node (ref "R24") (pin "1") (pinfunction "1_1") (pintype "passive"))
      (node (ref "U9") (pin "1") (pinfunction "A_1") (pintype "passive"))
    )
    (net (code "71") (name "Net-(U9-MT2)") (class "Default")
      (node (ref "R21") (pin "1") (pinfunction "1_1") (pintype "passive"))
      (node (ref "U9") (pin "6") (pinfunction "MT2_6") (pintype "passive"))
    )
    (net (code "72") (name "Net-(U10-A)") (class "Default")
      (node (ref "R25") (pin "1") (pinfunction "1_1") (pintype "passive"))
      (node (ref "U10") (pin "1") (pinfunction "A_1") (pintype "passive"))
    )
    (net (code "73") (name "Net-(U10-MT2)") (class "Default")
      (node (ref "R19") (pin "1") (pinfunction "1_1") (pintype "passive"))
      (node (ref "U10") (pin "6") (pinfunction "MT2_6") (pintype "passive"))
    )
    (net (code "74") (name "Net-(U11-A)") (class "Default")
      (node (ref "R26") (pin "2") (pinfunction "2_2") (pintype "passive"))
      (node (ref "U11") (pin "1") (pinfunction "A_1") (pintype "passive"))
    )
    (net (code "75") (name "Net-(U11-MT2)") (class "Default")
      (node (ref "R23") (pin "1") (pinfunction "1_1") (pintype "passive"))
      (node (ref "U11") (pin "6") (pinfunction "MT2_6") (pintype "passive"))
    )
    (net (code "76") (name "Net-(U12-A)") (class "Default")
      (node (ref "R27") (pin "2") (pinfunction "2_2") (pintype "passive"))
      (node (ref "U12") (pin "1") (pinfunction "A_1") (pintype "passive"))
    )
    (net (code "77") (name "Net-(U12-MT2)") (class "Default")
      (node (ref "R22") (pin "1") (pinfunction "1_1") (pintype "passive"))
      (node (ref "U12") (pin "6") (pinfunction "MT2_6") (pintype "passive"))
    )
    (net (code "78") (name "Net-(VALVE1A-KL)") (class "Default")
      (node (ref "T3") (pin "A") (pinfunction "A_A") (pintype "passive"))
      (node (ref "VALVE1") (pin "1") (pinfunction "KL_1") (pintype "passive"))
    )
    (net (code "79") (name "Net-(VALVE1B-KL)") (class "Default")
      (node (ref "T2") (pin "A") (pinfunction "A_A") (pintype "passive"))
      (node (ref "VALVE1") (pin "2") (pinfunction "KL_2") (pintype "passive"))
    )
    (net (code "80") (name "Net-(VALVE1C-KL)") (class "Default")
      (node (ref "T5") (pin "A") (pinfunction "A_A") (pintype "passive"))
      (node (ref "VALVE1") (pin "3") (pinfunction "KL_3") (pintype "passive"))
    )
    (net (code "81") (name "Net-(VALVE1D-KL)") (class "Default")
      (node (ref "T4") (pin "A") (pinfunction "A_A") (pintype "passive"))
      (node (ref "VALVE1") (pin "4") (pinfunction "KL_4") (pintype "passive"))
    )
    (net (code "82") (name "Net-(VALVE2A-KL)") (class "Default")
      (node (ref "T6") (pin "A") (pinfunction "A_A") (pintype "passive"))
      (node (ref "VALVE2") (pin "1") (pinfunction "KL_1") (pintype "passive"))
    )
    (net (code "83") (name "Net-(VALVE2B-KL)") (class "Default")
      (node (ref "T7") (pin "A") (pinfunction "A_A") (pintype "passive"))
      (node (ref "VALVE2") (pin "2") (pinfunction "KL_2") (pintype "passive"))
    )
    (net (code "84") (name "Net-(VALVE2C-KL)") (class "Default")
      (node (ref "T9") (pin "A") (pinfunction "A_A") (pintype "passive"))
      (node (ref "VALVE2") (pin "3") (pinfunction "KL_3") (pintype "passive"))
    )
    (net (code "85") (name "Net-(VALVE2D-KL)") (class "Default")
      (node (ref "T8") (pin "A") (pinfunction "A_A") (pintype "passive"))
      (node (ref "VALVE2") (pin "4") (pinfunction "KL_4") (pintype "passive"))
    )
    (net (code "86") (name "Net-(VALVE_PWRC-KL)") (class "Default")
      (node (ref "D3") (pin "A") (pinfunction "A_A") (pintype "passive"))
      (node (ref "VALVE_PWR") (pin "3") (pinfunction "KL_3") (pintype "passive"))
    )
    (net (code "87") (name "Net-(X2B-KL)") (class "Default")
      (node (ref "D4") (pin "C") (pinfunction "C_C") (pintype "passive"))
      (node (ref "D6") (pin "A") (pinfunction "A_A") (pintype "passive"))
      (node (ref "X2") (pin "2") (pinfunction "KL_2") (pintype "passive"))
    )
    (net (code "88") (name "V+") (class "Default")
      (node (ref "C7") (pin "1") (pinfunction "1_1") (pintype "passive"))
      (node (ref "D2") (pin "C") (pinfunction "C_C") (pintype "passive"))
      (node (ref "PC1") (pin "+") (pinfunction "+_+") (pintype "passive"))
      (node (ref "R3") (pin "1") (pinfunction "1_1") (pintype "passive"))
      (node (ref "U2") (pin "3") (pinfunction "IN_3") (pintype "input"))
      (node (ref "U3") (pin "3") (pinfunction "IN_3") (pintype "input"))
    )
    (net (code "89") (name "unconnected-(AT-MEGA328P-PU-(ADC2)PC2-Pad25)") (class "Default")
      (node (ref "AT-MEGA328P-PU") (pin "25") (pinfunction "(ADC2)PC2_25") (pintype "bidirectional"))
    )
    (net (code "90") (name "unconnected-(AT-MEGA328P-PU-(ADC3)PC3-Pad26)") (class "Default")
      (node (ref "AT-MEGA328P-PU") (pin "26") (pinfunction "(ADC3)PC3_26") (pintype "bidirectional"))
    )
    (net (code "91") (name "unconnected-(U$1-CTS-Pad9)") (class "Default")
      (node (ref "U$1") (pin "9") (pinfunction "CTS_9") (pintype "bidirectional"))
    )
    (net (code "92") (name "unconnected-(U$1-DCD-Pad12)") (class "Default")
      (node (ref "U$1") (pin "12") (pinfunction "DCD_12") (pintype "bidirectional"))
    )
    (net (code "93") (name "unconnected-(U$1-DSR-Pad10)") (class "Default")
      (node (ref "U$1") (pin "10") (pinfunction "DSR_10") (pintype "bidirectional"))
    )
    (net (code "94") (name "unconnected-(U$1-DTR-Pad13)") (class "Default")
      (node (ref "U$1") (pin "13") (pinfunction "DTR_13") (pintype "bidirectional"))
    )
    (net (code "95") (name "unconnected-(U$1-RI-Pad11)") (class "Default")
      (node (ref "U$1") (pin "11") (pinfunction "RI_11") (pintype "bidirectional"))
    )
    (net (code "96") (name "unconnected-(U$1-RS232-Pad15)") (class "Default")
      (node (ref "U$1") (pin "15") (pinfunction "RS232_15") (pintype "bidirectional"))
    )
    (net (code "97") (name "unconnected-(VALVE_PWRB-KL-Pad2)") (class "Default")
      (node (ref "VALVE_PWR") (pin "2") (pinfunction "KL_2") (pintype "passive"))
    )
  )
)
